# SAMC21_Xplained_Pro_Level_Converters.net
KiCad netlist of a schematic drawn in Altium Designer
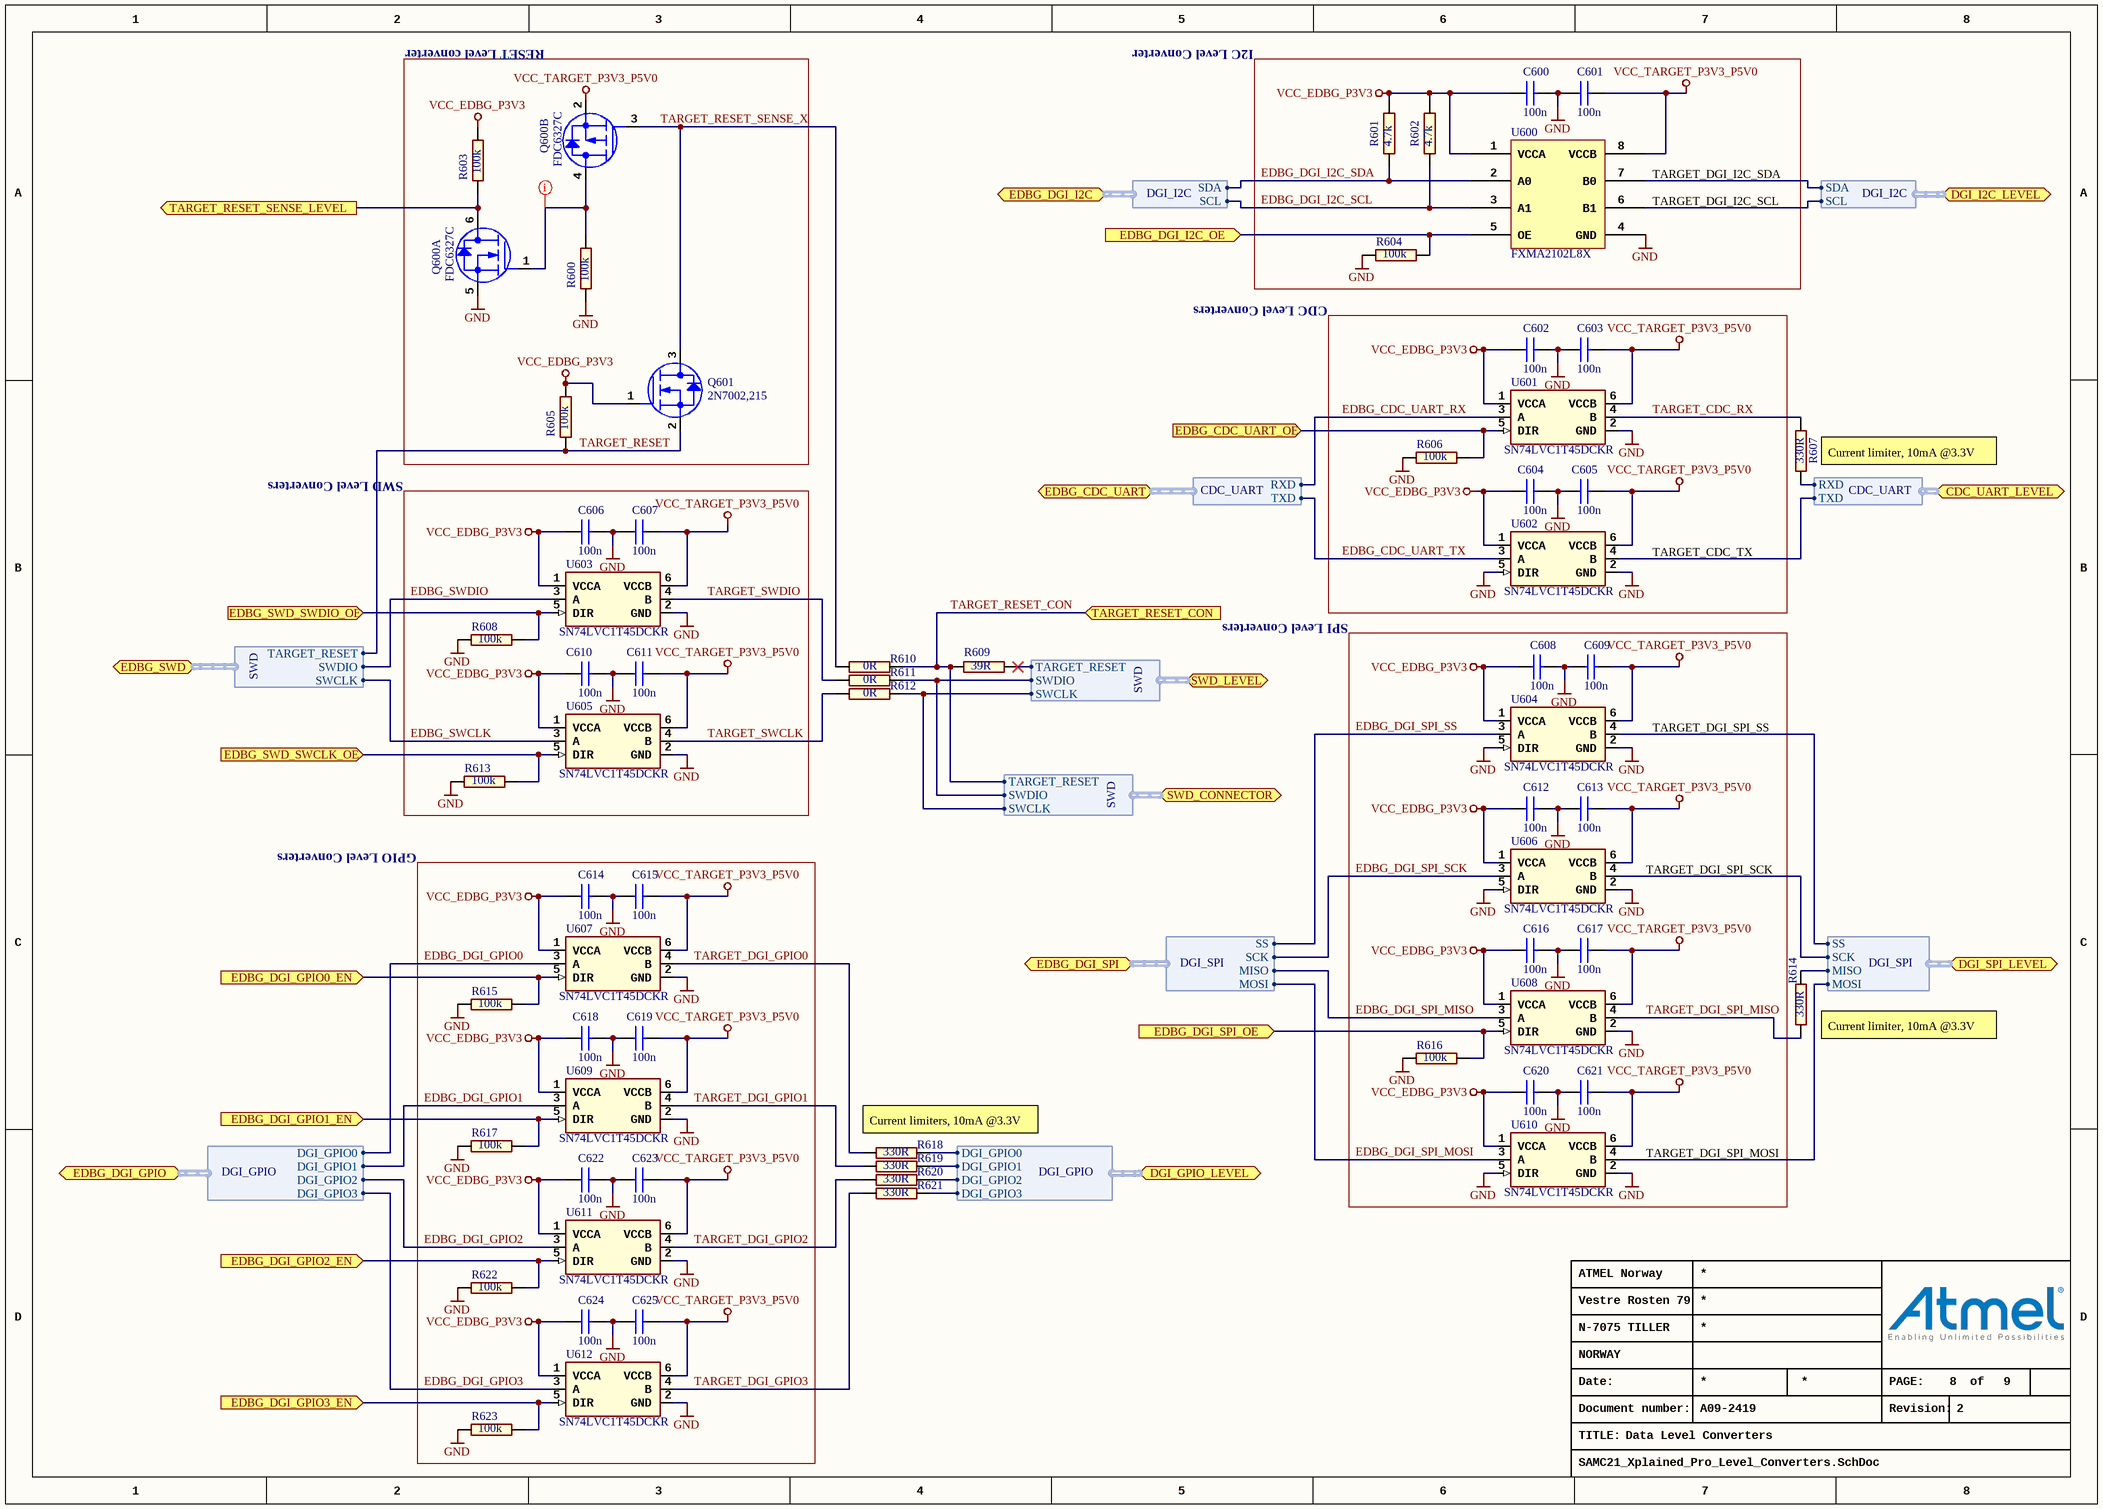
[diagram p0: SAMC21_Xplained_Pro_Level_Converters.SchDoc]

(export (version "E")
  (design (tool "Eeschema 10.0.6"))
  (components
    (comp (ref "C600")
      (value "100n")
      (footprint "AP1-00053")
      (description "Ceramic capacitor, SMD 0402, X7R, 16V, +/-10%")
      (fields (field (name "TOLERANCE") "16V, +/-10%") (field (name "MANUFACTURER") "Kemet"))
      (libsource (lib "AltiumDbLib") (part "CAP-NONPOL"))
    )
    (comp (ref "C601")
      (value "100n")
      (footprint "AP1-00053")
      (description "Ceramic capacitor, SMD 0402, X7R, 16V, +/-10%")
      (fields (field (name "TOLERANCE") "16V, +/-10%") (field (name "MANUFACTURER") "Kemet"))
      (libsource (lib "AltiumDbLib") (part "CAP-NONPOL"))
    )
    (comp (ref "C602")
      (value "100n")
      (footprint "AP1-00053")
      (description "Ceramic capacitor, SMD 0402, X7R, 16V, +/-10%")
      (fields (field (name "TOLERANCE") "16V, +/-10%") (field (name "MANUFACTURER") "Kemet"))
      (libsource (lib "AltiumDbLib") (part "CAP-NONPOL"))
    )
    (comp (ref "C603")
      (value "100n")
      (footprint "AP1-00053")
      (description "Ceramic capacitor, SMD 0402, X7R, 16V, +/-10%")
      (fields (field (name "TOLERANCE") "16V, +/-10%") (field (name "MANUFACTURER") "Kemet"))
      (libsource (lib "AltiumDbLib") (part "CAP-NONPOL"))
    )
    (comp (ref "C604")
      (value "100n")
      (footprint "AP1-00053")
      (description "Ceramic capacitor, SMD 0402, X7R, 16V, +/-10%")
      (fields (field (name "TOLERANCE") "16V, +/-10%") (field (name "MANUFACTURER") "Kemet"))
      (libsource (lib "AltiumDbLib") (part "CAP-NONPOL"))
    )
    (comp (ref "C605")
      (value "100n")
      (footprint "AP1-00053")
      (description "Ceramic capacitor, SMD 0402, X7R, 16V, +/-10%")
      (fields (field (name "TOLERANCE") "16V, +/-10%") (field (name "MANUFACTURER") "Kemet"))
      (libsource (lib "AltiumDbLib") (part "CAP-NONPOL"))
    )
    (comp (ref "C606")
      (value "100n")
      (footprint "AP1-00053")
      (description "Ceramic capacitor, SMD 0402, X7R, 16V, +/-10%")
      (fields (field (name "TOLERANCE") "16V, +/-10%") (field (name "MANUFACTURER") "Kemet"))
      (libsource (lib "AltiumDbLib") (part "CAP-NONPOL"))
    )
    (comp (ref "C607")
      (value "100n")
      (footprint "AP1-00053")
      (description "Ceramic capacitor, SMD 0402, X7R, 16V, +/-10%")
      (fields (field (name "TOLERANCE") "16V, +/-10%") (field (name "MANUFACTURER") "Kemet"))
      (libsource (lib "AltiumDbLib") (part "CAP-NONPOL"))
    )
    (comp (ref "C608")
      (value "100n")
      (footprint "AP1-00053")
      (description "Ceramic capacitor, SMD 0402, X7R, 16V, +/-10%")
      (fields (field (name "TOLERANCE") "16V, +/-10%") (field (name "MANUFACTURER") "Kemet"))
      (libsource (lib "AltiumDbLib") (part "CAP-NONPOL"))
    )
    (comp (ref "C609")
      (value "100n")
      (footprint "AP1-00053")
      (description "Ceramic capacitor, SMD 0402, X7R, 16V, +/-10%")
      (fields (field (name "TOLERANCE") "16V, +/-10%") (field (name "MANUFACTURER") "Kemet"))
      (libsource (lib "AltiumDbLib") (part "CAP-NONPOL"))
    )
    (comp (ref "C610")
      (value "100n")
      (footprint "AP1-00053")
      (description "Ceramic capacitor, SMD 0402, X7R, 16V, +/-10%")
      (fields (field (name "TOLERANCE") "16V, +/-10%") (field (name "MANUFACTURER") "Kemet"))
      (libsource (lib "AltiumDbLib") (part "CAP-NONPOL"))
    )
    (comp (ref "C611")
      (value "100n")
      (footprint "AP1-00053")
      (description "Ceramic capacitor, SMD 0402, X7R, 16V, +/-10%")
      (fields (field (name "TOLERANCE") "16V, +/-10%") (field (name "MANUFACTURER") "Kemet"))
      (libsource (lib "AltiumDbLib") (part "CAP-NONPOL"))
    )
    (comp (ref "C612")
      (value "100n")
      (footprint "AP1-00053")
      (description "Ceramic capacitor, SMD 0402, X7R, 16V, +/-10%")
      (fields (field (name "TOLERANCE") "16V, +/-10%") (field (name "MANUFACTURER") "Kemet"))
      (libsource (lib "AltiumDbLib") (part "CAP-NONPOL"))
    )
    (comp (ref "C613")
      (value "100n")
      (footprint "AP1-00053")
      (description "Ceramic capacitor, SMD 0402, X7R, 16V, +/-10%")
      (fields (field (name "TOLERANCE") "16V, +/-10%") (field (name "MANUFACTURER") "Kemet"))
      (libsource (lib "AltiumDbLib") (part "CAP-NONPOL"))
    )
    (comp (ref "C614")
      (value "100n")
      (footprint "AP1-00053")
      (description "Ceramic capacitor, SMD 0402, X7R, 16V, +/-10%")
      (fields (field (name "TOLERANCE") "16V, +/-10%") (field (name "MANUFACTURER") "Kemet"))
      (libsource (lib "AltiumDbLib") (part "CAP-NONPOL"))
    )
    (comp (ref "C615")
      (value "100n")
      (footprint "AP1-00053")
      (description "Ceramic capacitor, SMD 0402, X7R, 16V, +/-10%")
      (fields (field (name "TOLERANCE") "16V, +/-10%") (field (name "MANUFACTURER") "Kemet"))
      (libsource (lib "AltiumDbLib") (part "CAP-NONPOL"))
    )
    (comp (ref "C616")
      (value "100n")
      (footprint "AP1-00053")
      (description "Ceramic capacitor, SMD 0402, X7R, 16V, +/-10%")
      (fields (field (name "TOLERANCE") "16V, +/-10%") (field (name "MANUFACTURER") "Kemet"))
      (libsource (lib "AltiumDbLib") (part "CAP-NONPOL"))
    )
    (comp (ref "C617")
      (value "100n")
      (footprint "AP1-00053")
      (description "Ceramic capacitor, SMD 0402, X7R, 16V, +/-10%")
      (fields (field (name "TOLERANCE") "16V, +/-10%") (field (name "MANUFACTURER") "Kemet"))
      (libsource (lib "AltiumDbLib") (part "CAP-NONPOL"))
    )
    (comp (ref "C618")
      (value "100n")
      (footprint "AP1-00053")
      (description "Ceramic capacitor, SMD 0402, X7R, 16V, +/-10%")
      (fields (field (name "TOLERANCE") "16V, +/-10%") (field (name "MANUFACTURER") "Kemet"))
      (libsource (lib "AltiumDbLib") (part "CAP-NONPOL"))
    )
    (comp (ref "C619")
      (value "100n")
      (footprint "AP1-00053")
      (description "Ceramic capacitor, SMD 0402, X7R, 16V, +/-10%")
      (fields (field (name "TOLERANCE") "16V, +/-10%") (field (name "MANUFACTURER") "Kemet"))
      (libsource (lib "AltiumDbLib") (part "CAP-NONPOL"))
    )
    (comp (ref "C620")
      (value "100n")
      (footprint "AP1-00053")
      (description "Ceramic capacitor, SMD 0402, X7R, 16V, +/-10%")
      (fields (field (name "TOLERANCE") "16V, +/-10%") (field (name "MANUFACTURER") "Kemet"))
      (libsource (lib "AltiumDbLib") (part "CAP-NONPOL"))
    )
    (comp (ref "C621")
      (value "100n")
      (footprint "AP1-00053")
      (description "Ceramic capacitor, SMD 0402, X7R, 16V, +/-10%")
      (fields (field (name "TOLERANCE") "16V, +/-10%") (field (name "MANUFACTURER") "Kemet"))
      (libsource (lib "AltiumDbLib") (part "CAP-NONPOL"))
    )
    (comp (ref "C622")
      (value "100n")
      (footprint "AP1-00053")
      (description "Ceramic capacitor, SMD 0402, X7R, 16V, +/-10%")
      (fields (field (name "TOLERANCE") "16V, +/-10%") (field (name "MANUFACTURER") "Kemet"))
      (libsource (lib "AltiumDbLib") (part "CAP-NONPOL"))
    )
    (comp (ref "C623")
      (value "100n")
      (footprint "AP1-00053")
      (description "Ceramic capacitor, SMD 0402, X7R, 16V, +/-10%")
      (fields (field (name "TOLERANCE") "16V, +/-10%") (field (name "MANUFACTURER") "Kemet"))
      (libsource (lib "AltiumDbLib") (part "CAP-NONPOL"))
    )
    (comp (ref "C624")
      (value "100n")
      (footprint "AP1-00053")
      (description "Ceramic capacitor, SMD 0402, X7R, 16V, +/-10%")
      (fields (field (name "TOLERANCE") "16V, +/-10%") (field (name "MANUFACTURER") "Kemet"))
      (libsource (lib "AltiumDbLib") (part "CAP-NONPOL"))
    )
    (comp (ref "C625")
      (value "100n")
      (footprint "AP1-00053")
      (description "Ceramic capacitor, SMD 0402, X7R, 16V, +/-10%")
      (fields (field (name "TOLERANCE") "16V, +/-10%") (field (name "MANUFACTURER") "Kemet"))
      (libsource (lib "AltiumDbLib") (part "CAP-NONPOL"))
    )
    (comp (ref "Q600")
      (value "FDC6327C")
      (footprint "AP5-00008")
      (fields (field (name "MANUFACTURER") "Fairchild") (field (name "Comment") "Farnell no: 9844856"))
      (libsource (lib "AltiumDbLib") (part "DUAL_NP_G1S2G2D2S1D1"))
    )
    (comp (ref "Q601")
      (value "2N7002,215")
      (footprint "AP5-00002")
      (description "N-Channel MOSFET. 60V, 0.300A continuous, 1.2A Peak. RDS(ON) = 3.8Ohm@VGS=4.5V, VGS(th)<2.5V")
      (fields (field (name "MANUFACTURER") "NXP") (field (name "Comment") "MOSFET_N_GSD"))
      (libsource (lib "AltiumDbLib") (part "MOSFET_N_GSD"))
    )
    (comp (ref "R600")
      (value "100k")
      (footprint "AP2-00011")
      (description "Thick film resistor, SMD 0402, 1/16W, 1%")
      (fields (field (name "TOLERANCE") "1 %") (field (name "Comment") "R2"))
      (libsource (lib "") (part "R2_2"))
    )
    (comp (ref "R601")
      (value "4.7k")
      (footprint "AP2-00011")
      (description "Thick film resistor, SMD 0402, 1/16W, 1%")
      (fields (field (name "TOLERANCE") "1 %") (field (name "Comment") "R2"))
      (libsource (lib "") (part "R2_2"))
    )
    (comp (ref "R602")
      (value "4.7k")
      (footprint "AP2-00011")
      (description "Thick film resistor, SMD 0402, 1/16W, 1%")
      (fields (field (name "TOLERANCE") "1 %") (field (name "Comment") "R2"))
      (libsource (lib "") (part "R2_2"))
    )
    (comp (ref "R603")
      (value "100k")
      (footprint "AP2-00011")
      (description "Thick film resistor, SMD 0402, 1/16W, 1%")
      (fields (field (name "TOLERANCE") "1 %") (field (name "Comment") "R2"))
      (libsource (lib "") (part "R2_2"))
    )
    (comp (ref "R604")
      (value "100k")
      (footprint "AP2-00011")
      (description "Thick film resistor, SMD 0402, 1/16W, 1%")
      (fields (field (name "TOLERANCE") "1 %") (field (name "Comment") "R2"))
      (libsource (lib "") (part "R2_1"))
    )
    (comp (ref "R605")
      (value "100k")
      (footprint "AP2-00011")
      (description "Thick film resistor, SMD 0402, 1/16W, 1%")
      (fields (field (name "TOLERANCE") "1 %") (field (name "Comment") "R2"))
      (libsource (lib "") (part "R2_2"))
    )
    (comp (ref "R606")
      (value "100k")
      (footprint "AP2-00011")
      (description "Thick film resistor, SMD 0402, 1/16W, 1%")
      (fields (field (name "TOLERANCE") "1 %") (field (name "Comment") "R2"))
      (libsource (lib "AltiumDbLib") (part "R2"))
    )
    (comp (ref "R607")
      (value "330R")
      (footprint "AP2-00011")
      (description "Thick film resistor, SMD 0402, 1/16W, 1%")
      (fields (field (name "TOLERANCE") "1 %") (field (name "Comment") "R2"))
      (libsource (lib "") (part "R2_2"))
    )
    (comp (ref "R608")
      (value "100k")
      (footprint "AP2-00011")
      (description "Thick film resistor, SMD 0402, 1/16W, 1%")
      (fields (field (name "TOLERANCE") "1 %") (field (name "Comment") "R2"))
      (libsource (lib "AltiumDbLib") (part "R2"))
    )
    (comp (ref "R609")
      (value "39R")
      (footprint "AP2-00011")
      (description "Thick film resistor, SMD 0402, 1/16W, 1%")
      (fields (field (name "TOLERANCE") "1 %") (field (name "Comment") "R2"))
      (libsource (lib "") (part "R2_3"))
    )
    (comp (ref "R610")
      (value "0R")
      (footprint "AP2-00000")
      (description "Thick film resistor, SMD 0402, 1/16W, 1%")
      (fields (field (name "TOLERANCE") "1 %") (field (name "Comment") "R2"))
      (libsource (lib "") (part "R2_1"))
    )
    (comp (ref "R611")
      (value "0R")
      (footprint "AP2-00000")
      (description "Thick film resistor, SMD 0402, 1/16W, 1%")
      (fields (field (name "TOLERANCE") "1 %") (field (name "Comment") "R2"))
      (libsource (lib "") (part "R2_1"))
    )
    (comp (ref "R612")
      (value "0R")
      (footprint "AP2-00000")
      (description "Thick film resistor, SMD 0402, 1/16W, 1%")
      (fields (field (name "TOLERANCE") "1 %") (field (name "Comment") "R2"))
      (libsource (lib "") (part "R2_1"))
    )
    (comp (ref "R613")
      (value "100k")
      (footprint "AP2-00011")
      (description "Thick film resistor, SMD 0402, 1/16W, 1%")
      (fields (field (name "TOLERANCE") "1 %") (field (name "Comment") "R2"))
      (libsource (lib "AltiumDbLib") (part "R2"))
    )
    (comp (ref "R614")
      (value "330R")
      (footprint "AP2-00011")
      (description "Thick film resistor, SMD 0402, 1/16W, 1%")
      (fields (field (name "TOLERANCE") "1 %") (field (name "Comment") "R2"))
      (libsource (lib "") (part "R2_2"))
    )
    (comp (ref "R615")
      (value "100k")
      (footprint "AP2-00011")
      (description "Thick film resistor, SMD 0402, 1/16W, 1%")
      (fields (field (name "TOLERANCE") "1 %") (field (name "Comment") "R2"))
      (libsource (lib "AltiumDbLib") (part "R2"))
    )
    (comp (ref "R616")
      (value "100k")
      (footprint "AP2-00011")
      (description "Thick film resistor, SMD 0402, 1/16W, 1%")
      (fields (field (name "TOLERANCE") "1 %") (field (name "Comment") "R2"))
      (libsource (lib "AltiumDbLib") (part "R2"))
    )
    (comp (ref "R617")
      (value "100k")
      (footprint "AP2-00011")
      (description "Thick film resistor, SMD 0402, 1/16W, 1%")
      (fields (field (name "TOLERANCE") "1 %") (field (name "Comment") "R2"))
      (libsource (lib "AltiumDbLib") (part "R2"))
    )
    (comp (ref "R618")
      (value "330R")
      (footprint "AP2-00011")
      (description "Thick film resistor, SMD 0402, 1/16W, 1%")
      (fields (field (name "TOLERANCE") "1 %") (field (name "Comment") "R2"))
      (libsource (lib "") (part "R2_1"))
    )
    (comp (ref "R619")
      (value "330R")
      (footprint "AP2-00011")
      (description "Thick film resistor, SMD 0402, 1/16W, 1%")
      (fields (field (name "TOLERANCE") "1 %") (field (name "Comment") "R2"))
      (libsource (lib "") (part "R2_1"))
    )
    (comp (ref "R620")
      (value "330R")
      (footprint "AP2-00011")
      (description "Thick film resistor, SMD 0402, 1/16W, 1%")
      (fields (field (name "TOLERANCE") "1 %") (field (name "Comment") "R2"))
      (libsource (lib "") (part "R2_1"))
    )
    (comp (ref "R621")
      (value "330R")
      (footprint "AP2-00011")
      (description "Thick film resistor, SMD 0402, 1/16W, 1%")
      (fields (field (name "TOLERANCE") "1 %") (field (name "Comment") "R2"))
      (libsource (lib "") (part "R2_1"))
    )
    (comp (ref "R622")
      (value "100k")
      (footprint "AP2-00011")
      (description "Thick film resistor, SMD 0402, 1/16W, 1%")
      (fields (field (name "TOLERANCE") "1 %") (field (name "Comment") "R2"))
      (libsource (lib "AltiumDbLib") (part "R2"))
    )
    (comp (ref "R623")
      (value "100k")
      (footprint "AP2-00011")
      (description "Thick film resistor, SMD 0402, 1/16W, 1%")
      (fields (field (name "TOLERANCE") "1 %") (field (name "Comment") "R2"))
      (libsource (lib "AltiumDbLib") (part "R2"))
    )
    (comp (ref "U600")
      (value "FXMA2102L8X")
      (footprint "AP6-00258")
      (description "Dual supply, 2-bit, voltage translator, buffer, repeater, isolator for I2C applications")
      (fields (field (name "MANUFACTURER") "Fairchild") (field (name "Comment") "FXMA2102"))
      (libsource (lib "AltiumDbLib") (part "FXMA2102"))
    )
    (comp (ref "U601")
      (value "SN74LVC1T45DCKR")
      (footprint "AP6-00015")
      (description "Single-Bit Dual-Supply Bus Transceiver with Configurable Voltage Translation and 3-State Outputs")
      (fields (field (name "MANUFACTURER") "Texas Instruments"))
      (libsource (lib "AltiumDbLib") (part "SN74LVC1T45DCKR"))
    )
    (comp (ref "U602")
      (value "SN74LVC1T45DCKR")
      (footprint "AP6-00015")
      (description "Single-Bit Dual-Supply Bus Transceiver with Configurable Voltage Translation and 3-State Outputs")
      (fields (field (name "MANUFACTURER") "Texas Instruments"))
      (libsource (lib "AltiumDbLib") (part "SN74LVC1T45DCKR"))
    )
    (comp (ref "U603")
      (value "SN74LVC1T45DCKR")
      (footprint "AP6-00015")
      (description "Single-Bit Dual-Supply Bus Transceiver with Configurable Voltage Translation and 3-State Outputs")
      (fields (field (name "MANUFACTURER") "Texas Instruments"))
      (libsource (lib "AltiumDbLib") (part "SN74LVC1T45DCKR"))
    )
    (comp (ref "U604")
      (value "SN74LVC1T45DCKR")
      (footprint "AP6-00015")
      (description "Single-Bit Dual-Supply Bus Transceiver with Configurable Voltage Translation and 3-State Outputs")
      (fields (field (name "MANUFACTURER") "Texas Instruments"))
      (libsource (lib "AltiumDbLib") (part "SN74LVC1T45DCKR"))
    )
    (comp (ref "U605")
      (value "SN74LVC1T45DCKR")
      (footprint "AP6-00015")
      (description "Single-Bit Dual-Supply Bus Transceiver with Configurable Voltage Translation and 3-State Outputs")
      (fields (field (name "MANUFACTURER") "Texas Instruments"))
      (libsource (lib "AltiumDbLib") (part "SN74LVC1T45DCKR"))
    )
    (comp (ref "U606")
      (value "SN74LVC1T45DCKR")
      (footprint "AP6-00015")
      (description "Single-Bit Dual-Supply Bus Transceiver with Configurable Voltage Translation and 3-State Outputs")
      (fields (field (name "MANUFACTURER") "Texas Instruments"))
      (libsource (lib "AltiumDbLib") (part "SN74LVC1T45DCKR"))
    )
    (comp (ref "U607")
      (value "SN74LVC1T45DCKR")
      (footprint "AP6-00015")
      (description "Single-Bit Dual-Supply Bus Transceiver with Configurable Voltage Translation and 3-State Outputs")
      (fields (field (name "MANUFACTURER") "Texas Instruments"))
      (libsource (lib "AltiumDbLib") (part "SN74LVC1T45DCKR"))
    )
    (comp (ref "U608")
      (value "SN74LVC1T45DCKR")
      (footprint "AP6-00015")
      (description "Single-Bit Dual-Supply Bus Transceiver with Configurable Voltage Translation and 3-State Outputs")
      (fields (field (name "MANUFACTURER") "Texas Instruments"))
      (libsource (lib "AltiumDbLib") (part "SN74LVC1T45DCKR"))
    )
    (comp (ref "U609")
      (value "SN74LVC1T45DCKR")
      (footprint "AP6-00015")
      (description "Single-Bit Dual-Supply Bus Transceiver with Configurable Voltage Translation and 3-State Outputs")
      (fields (field (name "MANUFACTURER") "Texas Instruments"))
      (libsource (lib "AltiumDbLib") (part "SN74LVC1T45DCKR"))
    )
    (comp (ref "U610")
      (value "SN74LVC1T45DCKR")
      (footprint "AP6-00015")
      (description "Single-Bit Dual-Supply Bus Transceiver with Configurable Voltage Translation and 3-State Outputs")
      (fields (field (name "MANUFACTURER") "Texas Instruments"))
      (libsource (lib "AltiumDbLib") (part "SN74LVC1T45DCKR"))
    )
    (comp (ref "U611")
      (value "SN74LVC1T45DCKR")
      (footprint "AP6-00015")
      (description "Single-Bit Dual-Supply Bus Transceiver with Configurable Voltage Translation and 3-State Outputs")
      (fields (field (name "MANUFACTURER") "Texas Instruments"))
      (libsource (lib "AltiumDbLib") (part "SN74LVC1T45DCKR"))
    )
    (comp (ref "U612")
      (value "SN74LVC1T45DCKR")
      (footprint "AP6-00015")
      (description "Single-Bit Dual-Supply Bus Transceiver with Configurable Voltage Translation and 3-State Outputs")
      (fields (field (name "MANUFACTURER") "Texas Instruments"))
      (libsource (lib "AltiumDbLib") (part "SN74LVC1T45DCKR"))
    )
  )
  (nets
    (net (code "6") (name "/EDBG_CDC_UART_OE") (class "Default")
      (node (ref "R606") (pin "1") (pinfunction "1_1") (pintype "passive"))
      (node (ref "U601") (pin "5") (pinfunction "DIR_5") (pintype "input"))
    )
    (net (code "7") (name "/EDBG_CDC_UART_RX") (class "Default")
      (node (ref "U601") (pin "3") (pinfunction "A_3") (pintype "bidirectional"))
    )
    (net (code "8") (name "/EDBG_CDC_UART_TX") (class "Default")
      (node (ref "U602") (pin "3") (pinfunction "A_3") (pintype "bidirectional"))
    )
    (net (code "9") (name "/EDBG_DGI_GPIO0") (class "Default")
      (node (ref "U607") (pin "3") (pinfunction "A_3") (pintype "bidirectional"))
    )
    (net (code "10") (name "/EDBG_DGI_GPIO0_EN") (class "Default")
      (node (ref "R615") (pin "1") (pinfunction "1_1") (pintype "passive"))
      (node (ref "U607") (pin "5") (pinfunction "DIR_5") (pintype "input"))
    )
    (net (code "11") (name "/EDBG_DGI_GPIO1") (class "Default")
      (node (ref "U609") (pin "3") (pinfunction "A_3") (pintype "bidirectional"))
    )
    (net (code "12") (name "/EDBG_DGI_GPIO1_EN") (class "Default")
      (node (ref "R617") (pin "1") (pinfunction "1_1") (pintype "passive"))
      (node (ref "U609") (pin "5") (pinfunction "DIR_5") (pintype "input"))
    )
    (net (code "13") (name "/EDBG_DGI_GPIO2") (class "Default")
      (node (ref "U611") (pin "3") (pinfunction "A_3") (pintype "bidirectional"))
    )
    (net (code "14") (name "/EDBG_DGI_GPIO2_EN") (class "Default")
      (node (ref "R622") (pin "1") (pinfunction "1_1") (pintype "passive"))
      (node (ref "U611") (pin "5") (pinfunction "DIR_5") (pintype "input"))
    )
    (net (code "15") (name "/EDBG_DGI_GPIO3") (class "Default")
      (node (ref "U612") (pin "3") (pinfunction "A_3") (pintype "bidirectional"))
    )
    (net (code "16") (name "/EDBG_DGI_GPIO3_EN") (class "Default")
      (node (ref "R623") (pin "1") (pinfunction "1_1") (pintype "passive"))
      (node (ref "U612") (pin "5") (pinfunction "DIR_5") (pintype "input"))
    )
    (net (code "17") (name "/EDBG_DGI_I2C_OE") (class "Default")
      (node (ref "R604") (pin "2") (pinfunction "2_2") (pintype "passive"))
      (node (ref "U600") (pin "5") (pinfunction "OE_5") (pintype "passive"))
    )
    (net (code "18") (name "/EDBG_DGI_I2C_SCL") (class "Default")
      (node (ref "R602") (pin "1") (pinfunction "1_1") (pintype "passive"))
      (node (ref "U600") (pin "3") (pinfunction "A1_3") (pintype "open_collector"))
    )
    (net (code "19") (name "/EDBG_DGI_I2C_SDA") (class "Default")
      (node (ref "R601") (pin "1") (pinfunction "1_1") (pintype "passive"))
      (node (ref "U600") (pin "2") (pinfunction "A0_2") (pintype "open_collector"))
    )
    (net (code "20") (name "/EDBG_DGI_SPI_MISO") (class "Default")
      (node (ref "U608") (pin "3") (pinfunction "A_3") (pintype "bidirectional"))
    )
    (net (code "21") (name "/EDBG_DGI_SPI_MOSI") (class "Default")
      (node (ref "U610") (pin "3") (pinfunction "A_3") (pintype "bidirectional"))
    )
    (net (code "22") (name "/EDBG_DGI_SPI_OE") (class "Default")
      (node (ref "R616") (pin "1") (pinfunction "1_1") (pintype "passive"))
      (node (ref "U608") (pin "5") (pinfunction "DIR_5") (pintype "input"))
    )
    (net (code "23") (name "/EDBG_DGI_SPI_SCK") (class "Default")
      (node (ref "U606") (pin "3") (pinfunction "A_3") (pintype "bidirectional"))
    )
    (net (code "24") (name "/EDBG_DGI_SPI_SS") (class "Default")
      (node (ref "U604") (pin "3") (pinfunction "A_3") (pintype "bidirectional"))
    )
    (net (code "25") (name "/EDBG_SWCLK") (class "Default")
      (node (ref "U605") (pin "3") (pinfunction "A_3") (pintype "bidirectional"))
    )
    (net (code "26") (name "/EDBG_SWDIO") (class "Default")
      (node (ref "U603") (pin "3") (pinfunction "A_3") (pintype "bidirectional"))
    )
    (net (code "27") (name "/EDBG_SWD_SWCLK_OE") (class "Default")
      (node (ref "R613") (pin "1") (pinfunction "1_1") (pintype "passive"))
      (node (ref "U605") (pin "5") (pinfunction "DIR_5") (pintype "input"))
    )
    (net (code "28") (name "/EDBG_SWD_SWDIO_OE") (class "Default")
      (node (ref "R608") (pin "1") (pinfunction "1_1") (pintype "passive"))
      (node (ref "U603") (pin "5") (pinfunction "DIR_5") (pintype "input"))
    )
    (net (code "29") (name "/TARGET_CDC_RX") (class "Default")
      (node (ref "R607") (pin "2") (pinfunction "2_2") (pintype "passive"))
      (node (ref "U601") (pin "4") (pinfunction "B_4") (pintype "bidirectional"))
    )
    (net (code "30") (name "/TARGET_DGI_GPIO0") (class "Default")
      (node (ref "R618") (pin "1") (pinfunction "1_1") (pintype "passive"))
      (node (ref "U607") (pin "4") (pinfunction "B_4") (pintype "bidirectional"))
    )
    (net (code "31") (name "/TARGET_DGI_GPIO1") (class "Default")
      (node (ref "R619") (pin "1") (pinfunction "1_1") (pintype "passive"))
      (node (ref "U609") (pin "4") (pinfunction "B_4") (pintype "bidirectional"))
    )
    (net (code "32") (name "/TARGET_DGI_GPIO2") (class "Default")
      (node (ref "R620") (pin "1") (pinfunction "1_1") (pintype "passive"))
      (node (ref "U611") (pin "4") (pinfunction "B_4") (pintype "bidirectional"))
    )
    (net (code "33") (name "/TARGET_DGI_GPIO3") (class "Default")
      (node (ref "R621") (pin "1") (pinfunction "1_1") (pintype "passive"))
      (node (ref "U612") (pin "4") (pinfunction "B_4") (pintype "bidirectional"))
    )
    (net (code "34") (name "/TARGET_DGI_SPI_MISO") (class "Default")
      (node (ref "R614") (pin "1") (pinfunction "1_1") (pintype "passive"))
      (node (ref "U608") (pin "4") (pinfunction "B_4") (pintype "bidirectional"))
    )
    (net (code "35") (name "/TARGET_RESET") (class "Default")
      (node (ref "Q601") (pin "2") (pinfunction "S_2") (pintype "passive"))
      (node (ref "R605") (pin "1") (pinfunction "1_1") (pintype "passive"))
    )
    (net (code "36") (name "/TARGET_RESET_CON") (class "Default")
      (node (ref "R609") (pin "1") (pinfunction "1_1") (pintype "passive"))
      (node (ref "R610") (pin "2") (pinfunction "2_2") (pintype "passive"))
    )
    (net (code "37") (name "/TARGET_RESET_SENSE_LEVEL") (class "Default")
      (node (ref "Q600") (pin "6") (pinfunction "D_6") (pintype "passive"))
      (node (ref "R603") (pin "1") (pinfunction "1_1") (pintype "passive"))
    )
    (net (code "38") (name "/TARGET_RESET_SENSE_X") (class "Default")
      (node (ref "Q600") (pin "3") (pinfunction "G_3") (pintype "passive"))
      (node (ref "Q601") (pin "3") (pinfunction "D_3") (pintype "passive"))
      (node (ref "R610") (pin "1") (pinfunction "1_1") (pintype "passive"))
    )
    (net (code "39") (name "/TARGET_SWCLK") (class "Default")
      (node (ref "R612") (pin "1") (pinfunction "1_1") (pintype "passive"))
      (node (ref "U605") (pin "4") (pinfunction "B_4") (pintype "bidirectional"))
    )
    (net (code "40") (name "/TARGET_SWDIO") (class "Default")
      (node (ref "R611") (pin "1") (pinfunction "1_1") (pintype "passive"))
      (node (ref "U603") (pin "4") (pinfunction "B_4") (pintype "bidirectional"))
    )
    (net (code "46") (name "GND") (class "Default")
      (node (ref "C600") (pin "2") (pinfunction "2_2") (pintype "passive"))
      (node (ref "C601") (pin "1") (pinfunction "1_1") (pintype "passive"))
      (node (ref "C602") (pin "2") (pinfunction "2_2") (pintype "passive"))
      (node (ref "C603") (pin "1") (pinfunction "1_1") (pintype "passive"))
      (node (ref "C604") (pin "2") (pinfunction "2_2") (pintype "passive"))
      (node (ref "C605") (pin "1") (pinfunction "1_1") (pintype "passive"))
      (node (ref "C606") (pin "2") (pinfunction "2_2") (pintype "passive"))
      (node (ref "C607") (pin "1") (pinfunction "1_1") (pintype "passive"))
      (node (ref "C608") (pin "2") (pinfunction "2_2") (pintype "passive"))
      (node (ref "C609") (pin "1") (pinfunction "1_1") (pintype "passive"))
      (node (ref "C610") (pin "2") (pinfunction "2_2") (pintype "passive"))
      (node (ref "C611") (pin "1") (pinfunction "1_1") (pintype "passive"))
      (node (ref "C612") (pin "2") (pinfunction "2_2") (pintype "passive"))
      (node (ref "C613") (pin "1") (pinfunction "1_1") (pintype "passive"))
      (node (ref "C614") (pin "2") (pinfunction "2_2") (pintype "passive"))
      (node (ref "C615") (pin "1") (pinfunction "1_1") (pintype "passive"))
      (node (ref "C616") (pin "2") (pinfunction "2_2") (pintype "passive"))
      (node (ref "C617") (pin "1") (pinfunction "1_1") (pintype "passive"))
      (node (ref "C618") (pin "2") (pinfunction "2_2") (pintype "passive"))
      (node (ref "C619") (pin "1") (pinfunction "1_1") (pintype "passive"))
      (node (ref "C620") (pin "2") (pinfunction "2_2") (pintype "passive"))
      (node (ref "C621") (pin "1") (pinfunction "1_1") (pintype "passive"))
      (node (ref "C622") (pin "2") (pinfunction "2_2") (pintype "passive"))
      (node (ref "C623") (pin "1") (pinfunction "1_1") (pintype "passive"))
      (node (ref "C624") (pin "2") (pinfunction "2_2") (pintype "passive"))
      (node (ref "C625") (pin "1") (pinfunction "1_1") (pintype "passive"))
      (node (ref "Q600") (pin "5") (pinfunction "S_5") (pintype "passive"))
      (node (ref "R600") (pin "1") (pinfunction "1_1") (pintype "passive"))
      (node (ref "R604") (pin "1") (pinfunction "1_1") (pintype "passive"))
      (node (ref "R606") (pin "2") (pinfunction "2_2") (pintype "passive"))
      (node (ref "R608") (pin "2") (pinfunction "2_2") (pintype "passive"))
      (node (ref "R613") (pin "2") (pinfunction "2_2") (pintype "passive"))
      (node (ref "R615") (pin "2") (pinfunction "2_2") (pintype "passive"))
      (node (ref "R616") (pin "2") (pinfunction "2_2") (pintype "passive"))
      (node (ref "R617") (pin "2") (pinfunction "2_2") (pintype "passive"))
      (node (ref "R622") (pin "2") (pinfunction "2_2") (pintype "passive"))
      (node (ref "R623") (pin "2") (pinfunction "2_2") (pintype "passive"))
      (node (ref "U600") (pin "4") (pinfunction "GND_4") (pintype "power_in"))
      (node (ref "U601") (pin "2") (pinfunction "GND_2") (pintype "power_in"))
      (node (ref "U602") (pin "2") (pinfunction "GND_2") (pintype "power_in"))
      (node (ref "U602") (pin "5") (pinfunction "DIR_5") (pintype "input"))
      (node (ref "U603") (pin "2") (pinfunction "GND_2") (pintype "power_in"))
      (node (ref "U604") (pin "2") (pinfunction "GND_2") (pintype "power_in"))
      (node (ref "U604") (pin "5") (pinfunction "DIR_5") (pintype "input"))
      (node (ref "U605") (pin "2") (pinfunction "GND_2") (pintype "power_in"))
      (node (ref "U606") (pin "2") (pinfunction "GND_2") (pintype "power_in"))
      (node (ref "U606") (pin "5") (pinfunction "DIR_5") (pintype "input"))
      (node (ref "U607") (pin "2") (pinfunction "GND_2") (pintype "power_in"))
      (node (ref "U608") (pin "2") (pinfunction "GND_2") (pintype "power_in"))
      (node (ref "U609") (pin "2") (pinfunction "GND_2") (pintype "power_in"))
      (node (ref "U610") (pin "2") (pinfunction "GND_2") (pintype "power_in"))
      (node (ref "U610") (pin "5") (pinfunction "DIR_5") (pintype "input"))
      (node (ref "U611") (pin "2") (pinfunction "GND_2") (pintype "power_in"))
      (node (ref "U612") (pin "2") (pinfunction "GND_2") (pintype "power_in"))
    )
    (net (code "47") (name "Net-(Q600A-G)") (class "Default")
      (node (ref "Q600") (pin "1") (pinfunction "G_1") (pintype "passive"))
      (node (ref "Q600") (pin "4") (pinfunction "D_4") (pintype "passive"))
      (node (ref "R600") (pin "2") (pinfunction "2_2") (pintype "passive"))
    )
    (net (code "48") (name "VCC_EDBG_P3V3") (class "Default")
      (node (ref "C600") (pin "1") (pinfunction "1_1") (pintype "passive"))
      (node (ref "C602") (pin "1") (pinfunction "1_1") (pintype "passive"))
      (node (ref "C604") (pin "1") (pinfunction "1_1") (pintype "passive"))
      (node (ref "C606") (pin "1") (pinfunction "1_1") (pintype "passive"))
      (node (ref "C608") (pin "1") (pinfunction "1_1") (pintype "passive"))
      (node (ref "C610") (pin "1") (pinfunction "1_1") (pintype "passive"))
      (node (ref "C612") (pin "1") (pinfunction "1_1") (pintype "passive"))
      (node (ref "C614") (pin "1") (pinfunction "1_1") (pintype "passive"))
      (node (ref "C616") (pin "1") (pinfunction "1_1") (pintype "passive"))
      (node (ref "C618") (pin "1") (pinfunction "1_1") (pintype "passive"))
      (node (ref "C620") (pin "1") (pinfunction "1_1") (pintype "passive"))
      (node (ref "C622") (pin "1") (pinfunction "1_1") (pintype "passive"))
      (node (ref "C624") (pin "1") (pinfunction "1_1") (pintype "passive"))
      (node (ref "Q601") (pin "1") (pinfunction "G_1") (pintype "passive"))
      (node (ref "R601") (pin "2") (pinfunction "2_2") (pintype "passive"))
      (node (ref "R602") (pin "2") (pinfunction "2_2") (pintype "passive"))
      (node (ref "R603") (pin "2") (pinfunction "2_2") (pintype "passive"))
      (node (ref "R605") (pin "2") (pinfunction "2_2") (pintype "passive"))
      (node (ref "U600") (pin "1") (pinfunction "VCCA_1") (pintype "power_in"))
      (node (ref "U601") (pin "1") (pinfunction "VCCA_1") (pintype "power_in"))
      (node (ref "U602") (pin "1") (pinfunction "VCCA_1") (pintype "power_in"))
      (node (ref "U603") (pin "1") (pinfunction "VCCA_1") (pintype "power_in"))
      (node (ref "U604") (pin "1") (pinfunction "VCCA_1") (pintype "power_in"))
      (node (ref "U605") (pin "1") (pinfunction "VCCA_1") (pintype "power_in"))
      (node (ref "U606") (pin "1") (pinfunction "VCCA_1") (pintype "power_in"))
      (node (ref "U607") (pin "1") (pinfunction "VCCA_1") (pintype "power_in"))
      (node (ref "U608") (pin "1") (pinfunction "VCCA_1") (pintype "power_in"))
      (node (ref "U609") (pin "1") (pinfunction "VCCA_1") (pintype "power_in"))
      (node (ref "U610") (pin "1") (pinfunction "VCCA_1") (pintype "power_in"))
      (node (ref "U611") (pin "1") (pinfunction "VCCA_1") (pintype "power_in"))
      (node (ref "U612") (pin "1") (pinfunction "VCCA_1") (pintype "power_in"))
    )
    (net (code "49") (name "VCC_TARGET_P3V3_P5V0") (class "Default")
      (node (ref "C601") (pin "2") (pinfunction "2_2") (pintype "passive"))
      (node (ref "C603") (pin "2") (pinfunction "2_2") (pintype "passive"))
      (node (ref "C605") (pin "2") (pinfunction "2_2") (pintype "passive"))
      (node (ref "C607") (pin "2") (pinfunction "2_2") (pintype "passive"))
      (node (ref "C609") (pin "2") (pinfunction "2_2") (pintype "passive"))
      (node (ref "C611") (pin "2") (pinfunction "2_2") (pintype "passive"))
      (node (ref "C613") (pin "2") (pinfunction "2_2") (pintype "passive"))
      (node (ref "C615") (pin "2") (pinfunction "2_2") (pintype "passive"))
      (node (ref "C617") (pin "2") (pinfunction "2_2") (pintype "passive"))
      (node (ref "C619") (pin "2") (pinfunction "2_2") (pintype "passive"))
      (node (ref "C621") (pin "2") (pinfunction "2_2") (pintype "passive"))
      (node (ref "C623") (pin "2") (pinfunction "2_2") (pintype "passive"))
      (node (ref "C625") (pin "2") (pinfunction "2_2") (pintype "passive"))
      (node (ref "Q600") (pin "2") (pinfunction "S_2") (pintype "passive"))
      (node (ref "U600") (pin "8") (pinfunction "VCCB_8") (pintype "power_in"))
      (node (ref "U601") (pin "6") (pinfunction "VCCB_6") (pintype "power_in"))
      (node (ref "U602") (pin "6") (pinfunction "VCCB_6") (pintype "power_in"))
      (node (ref "U603") (pin "6") (pinfunction "VCCB_6") (pintype "power_in"))
      (node (ref "U604") (pin "6") (pinfunction "VCCB_6") (pintype "power_in"))
      (node (ref "U605") (pin "6") (pinfunction "VCCB_6") (pintype "power_in"))
      (node (ref "U606") (pin "6") (pinfunction "VCCB_6") (pintype "power_in"))
      (node (ref "U607") (pin "6") (pinfunction "VCCB_6") (pintype "power_in"))
      (node (ref "U608") (pin "6") (pinfunction "VCCB_6") (pintype "power_in"))
      (node (ref "U609") (pin "6") (pinfunction "VCCB_6") (pintype "power_in"))
      (node (ref "U610") (pin "6") (pinfunction "VCCB_6") (pintype "power_in"))
      (node (ref "U611") (pin "6") (pinfunction "VCCB_6") (pintype "power_in"))
      (node (ref "U612") (pin "6") (pinfunction "VCCB_6") (pintype "power_in"))
    )
    (net (code "50") (name "unconnected-(R607-Pad1)") (class "Default")
      (node (ref "R607") (pin "1") (pinfunction "1_1") (pintype "passive"))
    )
    (net (code "51") (name "unconnected-(R609-Pad2)") (class "Default")
      (node (ref "R609") (pin "2") (pinfunction "2_2") (pintype "passive+no_connect"))
    )
    (net (code "52") (name "unconnected-(R611-Pad2)") (class "Default")
      (node (ref "R611") (pin "2") (pinfunction "2_2") (pintype "passive"))
    )
    (net (code "53") (name "unconnected-(R612-Pad2)") (class "Default")
      (node (ref "R612") (pin "2") (pinfunction "2_2") (pintype "passive"))
    )
    (net (code "54") (name "unconnected-(R614-Pad2)") (class "Default")
      (node (ref "R614") (pin "2") (pinfunction "2_2") (pintype "passive"))
    )
    (net (code "55") (name "unconnected-(R618-Pad2)") (class "Default")
      (node (ref "R618") (pin "2") (pinfunction "2_2") (pintype "passive"))
    )
    (net (code "56") (name "unconnected-(R619-Pad2)") (class "Default")
      (node (ref "R619") (pin "2") (pinfunction "2_2") (pintype "passive"))
    )
    (net (code "57") (name "unconnected-(R620-Pad2)") (class "Default")
      (node (ref "R620") (pin "2") (pinfunction "2_2") (pintype "passive"))
    )
    (net (code "58") (name "unconnected-(R621-Pad2)") (class "Default")
      (node (ref "R621") (pin "2") (pinfunction "2_2") (pintype "passive"))
    )
    (net (code "59") (name "unconnected-(U600-B0-Pad7)") (class "Default")
      (node (ref "U600") (pin "7") (pinfunction "B0_7") (pintype "open_collector"))
    )
    (net (code "60") (name "unconnected-(U600-B1-Pad6)") (class "Default")
      (node (ref "U600") (pin "6") (pinfunction "B1_6") (pintype "open_collector"))
    )
    (net (code "61") (name "unconnected-(U602-B-Pad4)") (class "Default")
      (node (ref "U602") (pin "4") (pinfunction "B_4") (pintype "bidirectional"))
    )
    (net (code "62") (name "unconnected-(U604-B-Pad4)") (class "Default")
      (node (ref "U604") (pin "4") (pinfunction "B_4") (pintype "bidirectional"))
    )
    (net (code "63") (name "unconnected-(U606-B-Pad4)") (class "Default")
      (node (ref "U606") (pin "4") (pinfunction "B_4") (pintype "bidirectional"))
    )
    (net (code "64") (name "unconnected-(U610-B-Pad4)") (class "Default")
      (node (ref "U610") (pin "4") (pinfunction "B_4") (pintype "bidirectional"))
    )
  )
)
